# FPGA_Connect.net
KiCad netlist of a schematic drawn in Altium Designer
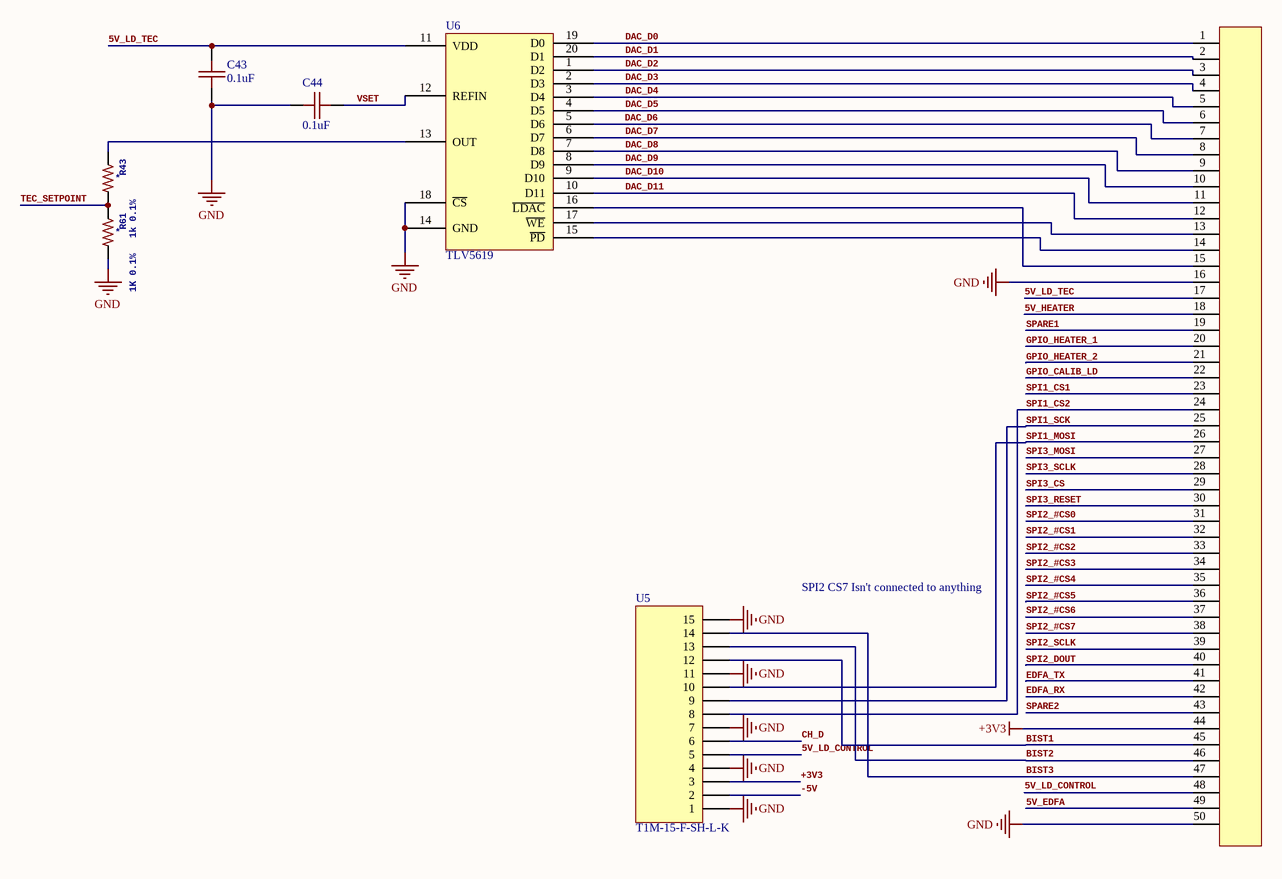
[diagram p0: FPGA Connect.SchDoc]

(export (version "E")
  (design (tool "Eeschema 10.0.6"))
  (components
    (comp (ref "C43")
      (value "0.1uF")
      (footprint "0402 B")
      (description "402 Capacitor")
      (libsource (lib "DaughterBoard") (part "CAP 0402"))
    )
    (comp (ref "C44")
      (value "0.1uF")
      (footprint "0402 B")
      (description "402 Capacitor")
      (libsource (lib "DaughterBoard") (part "CAP 0402"))
    )
    (comp (ref "CON5")
      (value "~")
      (footprint "LSEM-150-XX.X-X-DV-A-X-XX-TR")
      (description "SAMTEC connector SAMTEC_LSEM_V_50")
      (libsource (lib "DaughterBoard") (part "SAMTEC_LSEM_V_50"))
    )
    (comp (ref "R43")
      (value "1k 0.1%")
      (footprint "0402R")
      (description "RESISTOR, American symbol")
      (fields (field (name "NAME") "*"))
      (libsource (lib "rcl") (part "R-US_R0603"))
    )
    (comp (ref "R61")
      (value "1K 0.1%")
      (footprint "0402R")
      (description "RESISTOR, American symbol")
      (fields (field (name "NAME") "*"))
      (libsource (lib "rcl") (part "R-US_R0603"))
    )
    (comp (ref "U5")
      (value "T1M-15-F-SH-L-K")
      (footprint "T1M-15-F-SH-L-K")
      (libsource (lib "DaughterBoard") (part "T1M-15-F-SH-L-K"))
    )
    (comp (ref "U6")
      (value "TLV5619")
      (footprint "TSSOP-20")
      (libsource (lib "DaughterBoard") (part "TLV5619"))
    )
  )
  (nets
    (net (code "1") (name "+3V3") (class "Default")
      (node (ref "CON5") (pin "44") (pintype "passive"))
      (node (ref "U5") (pin "3") (pinfunction "3_3") (pintype "passive"))
    )
    (net (code "2") (name "/-5V") (class "Default")
      (node (ref "U5") (pin "2") (pinfunction "2_2") (pintype "passive"))
    )
    (net (code "3") (name "/5V_EDFA") (class "Default") (node (ref "CON5") (pin "49") (pintype "passive")))
    (net (code "4") (name "/5V_HEATER") (class "Default") (node (ref "CON5") (pin "18") (pintype "passive")))
    (net (code "5") (name "/5V_LD_CONTROL") (class "Default")
      (node (ref "CON5") (pin "48") (pintype "passive"))
      (node (ref "U5") (pin "5") (pinfunction "5_5") (pintype "passive"))
    )
    (net (code "6") (name "/5V_LD_TEC") (class "Default")
      (node (ref "C43") (pin "1") (pintype "passive"))
      (node (ref "CON5") (pin "17") (pintype "passive"))
      (node (ref "U6") (pin "11") (pinfunction "VDD_11") (pintype "passive"))
    )
    (net (code "7") (name "/BIST1") (class "Default")
      (node (ref "CON5") (pin "45") (pintype "passive"))
      (node (ref "U5") (pin "12") (pinfunction "12_12") (pintype "passive"))
    )
    (net (code "8") (name "/BIST2") (class "Default")
      (node (ref "CON5") (pin "46") (pintype "passive"))
      (node (ref "U5") (pin "13") (pinfunction "13_13") (pintype "passive"))
    )
    (net (code "9") (name "/BIST3") (class "Default")
      (node (ref "CON5") (pin "47") (pintype "passive"))
      (node (ref "U5") (pin "14") (pinfunction "14_14") (pintype "passive"))
    )
    (net (code "10") (name "/CH_D") (class "Default")
      (node (ref "U5") (pin "6") (pinfunction "6_6") (pintype "passive"))
    )
    (net (code "11") (name "/DAC_D0") (class "Default")
      (node (ref "CON5") (pin "1") (pintype "passive"))
      (node (ref "U6") (pin "19") (pinfunction "D0_19") (pintype "passive"))
    )
    (net (code "12") (name "/DAC_D1") (class "Default")
      (node (ref "CON5") (pin "2") (pintype "passive"))
      (node (ref "U6") (pin "20") (pinfunction "D1_20") (pintype "passive"))
    )
    (net (code "13") (name "/DAC_D2") (class "Default")
      (node (ref "CON5") (pin "3") (pintype "passive"))
      (node (ref "U6") (pin "1") (pinfunction "D2_1") (pintype "passive"))
    )
    (net (code "14") (name "/DAC_D3") (class "Default")
      (node (ref "CON5") (pin "4") (pintype "passive"))
      (node (ref "U6") (pin "2") (pinfunction "D3_2") (pintype "passive"))
    )
    (net (code "15") (name "/DAC_D4") (class "Default")
      (node (ref "CON5") (pin "5") (pintype "passive"))
      (node (ref "U6") (pin "3") (pinfunction "D4_3") (pintype "passive"))
    )
    (net (code "16") (name "/DAC_D5") (class "Default")
      (node (ref "CON5") (pin "6") (pintype "passive"))
      (node (ref "U6") (pin "4") (pinfunction "D5_4") (pintype "passive"))
    )
    (net (code "17") (name "/DAC_D6") (class "Default")
      (node (ref "CON5") (pin "7") (pintype "passive"))
      (node (ref "U6") (pin "5") (pinfunction "D6_5") (pintype "passive"))
    )
    (net (code "18") (name "/DAC_D7") (class "Default")
      (node (ref "CON5") (pin "8") (pintype "passive"))
      (node (ref "U6") (pin "6") (pinfunction "D7_6") (pintype "passive"))
    )
    (net (code "19") (name "/DAC_D8") (class "Default")
      (node (ref "CON5") (pin "9") (pintype "passive"))
      (node (ref "U6") (pin "7") (pinfunction "D8_7") (pintype "passive"))
    )
    (net (code "20") (name "/DAC_D9") (class "Default")
      (node (ref "CON5") (pin "10") (pintype "passive"))
      (node (ref "U6") (pin "8") (pinfunction "D9_8") (pintype "passive"))
    )
    (net (code "21") (name "/DAC_D10") (class "Default")
      (node (ref "CON5") (pin "11") (pintype "passive"))
      (node (ref "U6") (pin "9") (pinfunction "D10_9") (pintype "passive"))
    )
    (net (code "22") (name "/DAC_D11") (class "Default")
      (node (ref "CON5") (pin "12") (pintype "passive"))
      (node (ref "U6") (pin "10") (pinfunction "D11_10") (pintype "passive"))
    )
    (net (code "23") (name "/EDFA_RX") (class "Default") (node (ref "CON5") (pin "42") (pintype "passive")))
    (net (code "24") (name "/EDFA_TX") (class "Default") (node (ref "CON5") (pin "41") (pintype "passive")))
    (net (code "25") (name "/GPIO_CALIB_LD") (class "Default")
      (node (ref "CON5") (pin "22") (pintype "passive"))
    )
    (net (code "26") (name "/GPIO_HEATER_1") (class "Default")
      (node (ref "CON5") (pin "20") (pintype "passive"))
    )
    (net (code "27") (name "/GPIO_HEATER_2") (class "Default")
      (node (ref "CON5") (pin "21") (pintype "passive"))
    )
    (net (code "28") (name "/SPARE1") (class "Default") (node (ref "CON5") (pin "19") (pintype "passive")))
    (net (code "29") (name "/SPARE2") (class "Default") (node (ref "CON5") (pin "43") (pintype "passive")))
    (net (code "30") (name "/SPI1_CS1") (class "Default") (node (ref "CON5") (pin "23") (pintype "passive")))
    (net (code "32") (name "/SPI1_CS2") (class "Default")
      (node (ref "CON5") (pin "24") (pintype "passive"))
      (node (ref "U5") (pin "8") (pinfunction "8_8") (pintype "passive"))
    )
    (net (code "33") (name "/SPI1_MOSI") (class "Default")
      (node (ref "CON5") (pin "26") (pintype "passive"))
      (node (ref "U5") (pin "10") (pinfunction "10_10") (pintype "passive"))
    )
    (net (code "34") (name "/SPI1_SCK") (class "Default")
      (node (ref "CON5") (pin "25") (pintype "passive"))
      (node (ref "U5") (pin "9") (pinfunction "9_9") (pintype "passive"))
    )
    (net (code "35") (name "/SPI2_#CS0") (class "Default") (node (ref "CON5") (pin "31") (pintype "passive")))
    (net (code "36") (name "/SPI2_#CS1") (class "Default") (node (ref "CON5") (pin "32") (pintype "passive")))
    (net (code "37") (name "/SPI2_#CS2") (class "Default") (node (ref "CON5") (pin "33") (pintype "passive")))
    (net (code "38") (name "/SPI2_#CS3") (class "Default") (node (ref "CON5") (pin "34") (pintype "passive")))
    (net (code "39") (name "/SPI2_#CS4") (class "Default") (node (ref "CON5") (pin "35") (pintype "passive")))
    (net (code "40") (name "/SPI2_#CS5") (class "Default") (node (ref "CON5") (pin "36") (pintype "passive")))
    (net (code "41") (name "/SPI2_#CS6") (class "Default") (node (ref "CON5") (pin "37") (pintype "passive")))
    (net (code "42") (name "/SPI2_#CS7") (class "Default") (node (ref "CON5") (pin "38") (pintype "passive")))
    (net (code "43") (name "/SPI2_DOUT") (class "Default") (node (ref "CON5") (pin "40") (pintype "passive")))
    (net (code "44") (name "/SPI2_SCLK") (class "Default") (node (ref "CON5") (pin "39") (pintype "passive")))
    (net (code "45") (name "/SPI3_CS") (class "Default") (node (ref "CON5") (pin "29") (pintype "passive")))
    (net (code "46") (name "/SPI3_MOSI") (class "Default") (node (ref "CON5") (pin "27") (pintype "passive")))
    (net (code "47") (name "/SPI3_RESET") (class "Default")
      (node (ref "CON5") (pin "30") (pintype "passive"))
    )
    (net (code "48") (name "/SPI3_SCLK") (class "Default") (node (ref "CON5") (pin "28") (pintype "passive")))
    (net (code "49") (name "/TEC_SETPOINT") (class "Default")
      (node (ref "R43") (pin "2") (pinfunction "2_2") (pintype "passive"))
      (node (ref "R61") (pin "1") (pinfunction "1_1") (pintype "passive"))
    )
    (net (code "50") (name "/VSET") (class "Default")
      (node (ref "C44") (pin "1") (pintype "passive"))
      (node (ref "U6") (pin "12") (pinfunction "REFIN_12") (pintype "passive"))
    )
    (net (code "51") (name "GND") (class "Default")
      (node (ref "C43") (pin "2") (pintype "passive"))
      (node (ref "C44") (pin "2") (pintype "passive"))
      (node (ref "CON5") (pin "16") (pintype "passive"))
      (node (ref "CON5") (pin "50") (pintype "passive"))
      (node (ref "R61") (pin "2") (pinfunction "2_2") (pintype "passive"))
      (node (ref "U5") (pin "1") (pinfunction "1_1") (pintype "passive"))
      (node (ref "U5") (pin "11") (pinfunction "11_11") (pintype "passive"))
      (node (ref "U5") (pin "15") (pinfunction "15_15") (pintype "passive"))
      (node (ref "U5") (pin "4") (pinfunction "4_4") (pintype "passive"))
      (node (ref "U5") (pin "7") (pinfunction "7_7") (pintype "passive"))
      (node (ref "U6") (pin "14") (pinfunction "GND_14") (pintype "passive"))
      (node (ref "U6") (pin "18") (pinfunction "~{CS}_18") (pintype "passive"))
    )
    (net (code "52") (name "Net-(U6-OUT)") (class "Default")
      (node (ref "R43") (pin "1") (pinfunction "1_1") (pintype "passive"))
      (node (ref "U6") (pin "13") (pinfunction "OUT_13") (pintype "passive"))
    )
    (net (code "53") (name "Net-(U6-~{LDAC})") (class "Default")
      (node (ref "CON5") (pin "15") (pintype "passive"))
      (node (ref "U6") (pin "16") (pinfunction "~{LDAC}_16") (pintype "passive"))
    )
    (net (code "54") (name "Net-(U6-~{PD})") (class "Default")
      (node (ref "CON5") (pin "14") (pintype "passive"))
      (node (ref "U6") (pin "15") (pinfunction "~{PD}_15") (pintype "passive"))
    )
    (net (code "55") (name "Net-(U6-~{WE})") (class "Default")
      (node (ref "CON5") (pin "13") (pintype "passive"))
      (node (ref "U6") (pin "17") (pinfunction "~{WE}_17") (pintype "passive"))
    )
  )
)
